# Qwiic_Shield_for_Metro_M0.net
KiCad netlist of a schematic drawn in EAGLE
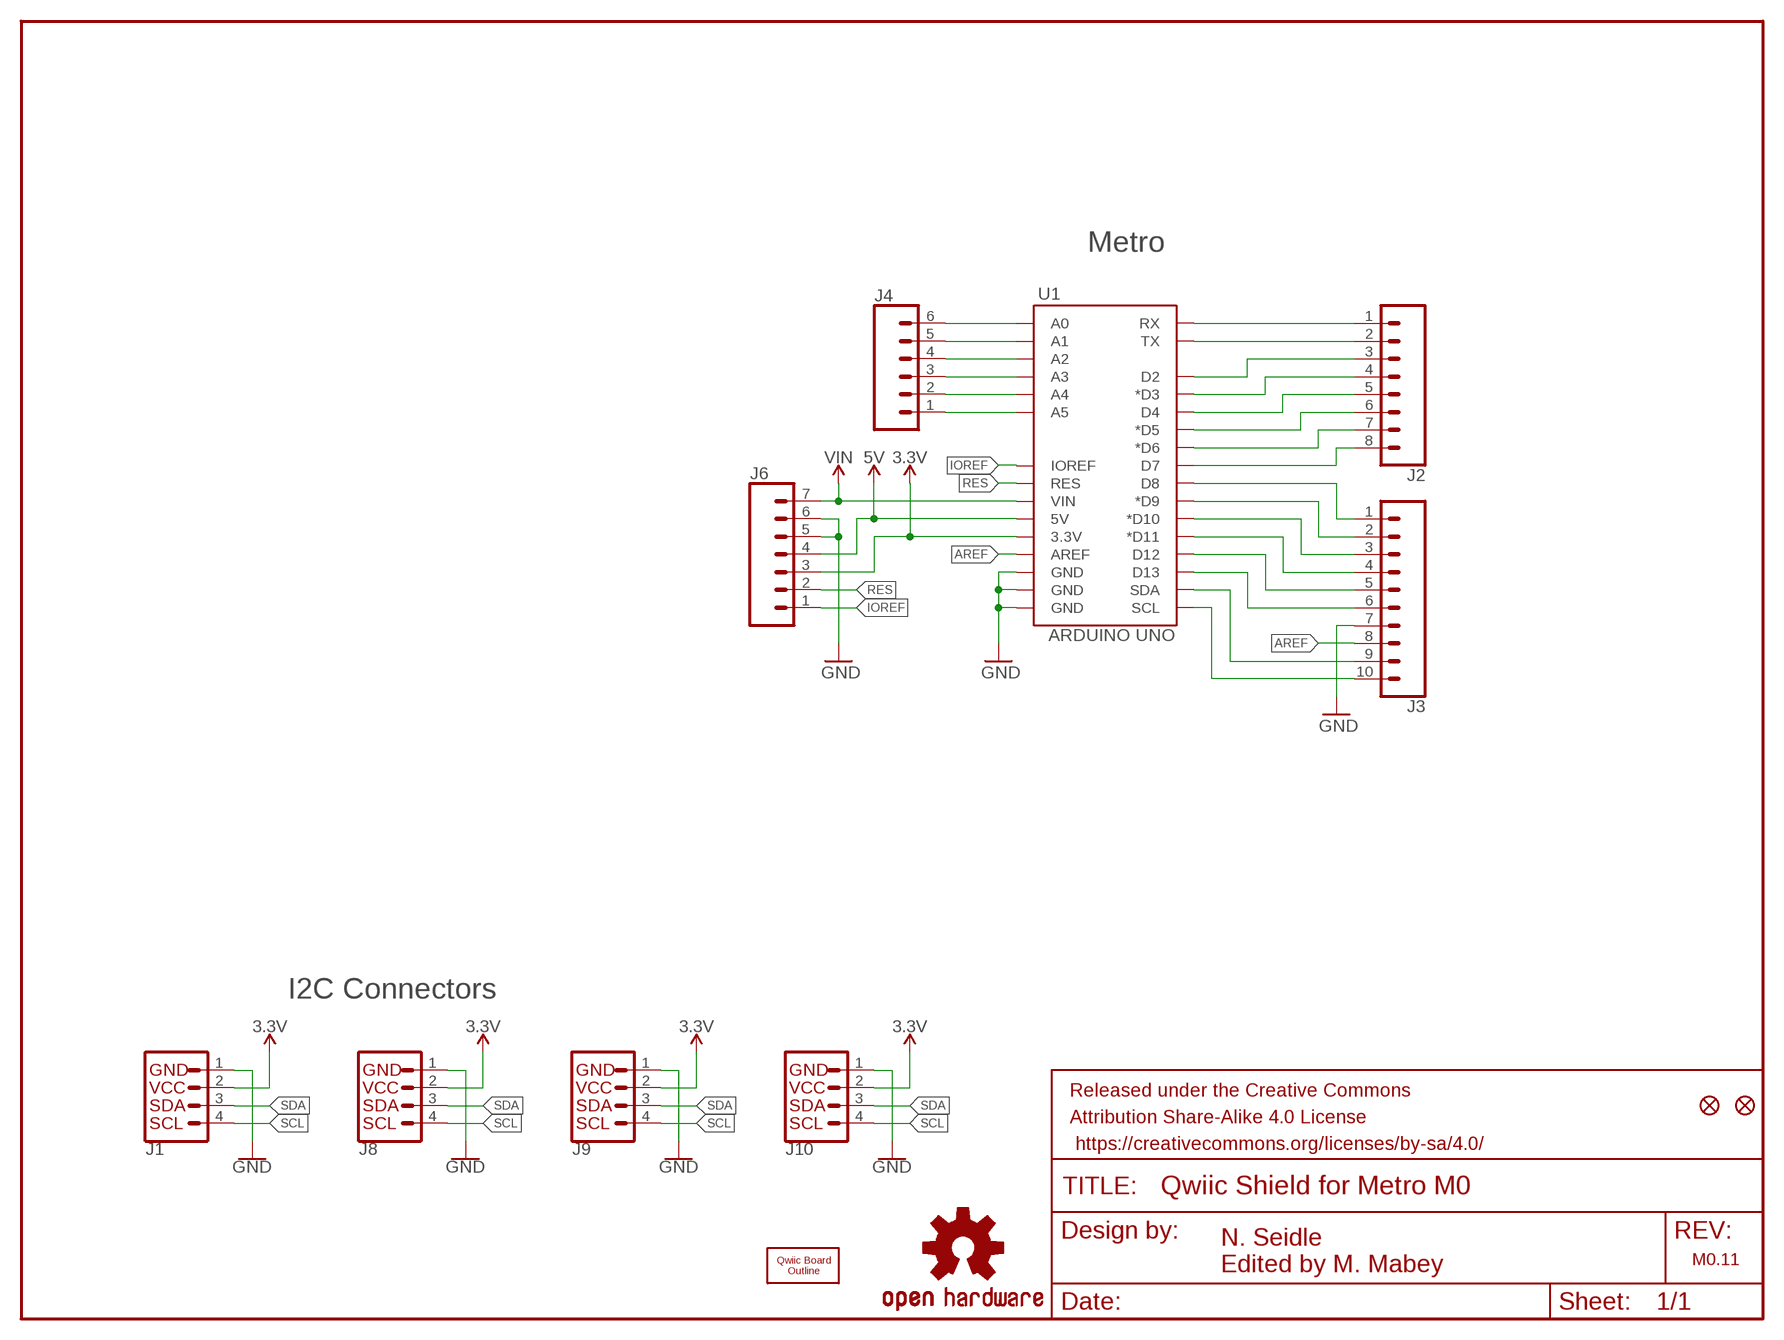
[diagram p0: schematic, sheet 1]

(export (version "E")
  (design (tool "Eeschema 10.0.6"))
  (components
    (comp (ref "FD1")
      (value "FIDUCIAL1X2")
      (footprint "eagle-import:FIDUCIAL-1X2")
      (libsource (lib "eagle-import") (part "FIDUCIAL1X2"))
    )
    (comp (ref "FD2")
      (value "FIDUCIAL1X2")
      (footprint "eagle-import:FIDUCIAL-1X2")
      (libsource (lib "eagle-import") (part "FIDUCIAL1X2"))
    )
    (comp (ref "FRAME1")
      (value "FRAME-LETTER")
      (footprint "eagle-import:CREATIVE_COMMONS")
      (libsource (lib "eagle-import") (part "FRAME-LETTER"))
    )
    (comp (ref "J1")
      (value "I2C_STANDARDJS-1MM")
      (footprint "eagle-import:1X04_1MM_RA")
      (libsource (lib "eagle-import") (part "I2C_STANDARDJS-1MM"))
    )
    (comp (ref "J2")
      (value "CONN_08NO_SILK_FEMALE_PTH")
      (footprint "eagle-import:1X08_NO_SILK")
      (libsource (lib "eagle-import") (part "CONN_08NO_SILK_FEMALE_PTH"))
    )
    (comp (ref "J3")
      (value "CONN_10NO_SILK_PTH_FEMALE")
      (footprint "eagle-import:1X10_NO_SILK")
      (libsource (lib "eagle-import") (part "CONN_10NO_SILK_PTH_FEMALE"))
    )
    (comp (ref "J4")
      (value "CONN_06NO_SILK_FEMALE_PTH")
      (footprint "eagle-import:1X06_NO_SILK")
      (libsource (lib "eagle-import") (part "CONN_06NO_SILK_FEMALE_PTH"))
    )
    (comp (ref "J6")
      (value "CONN_07NO_SILK")
      (footprint "eagle-import:1X07_NO_SILK")
      (libsource (lib "eagle-import") (part "CONN_07NO_SILK"))
    )
    (comp (ref "J8")
      (value "I2C_STANDARDJS-1MM")
      (footprint "eagle-import:1X04_1MM_RA")
      (libsource (lib "eagle-import") (part "I2C_STANDARDJS-1MM"))
    )
    (comp (ref "J9")
      (value "I2C_STANDARDJS-1MM")
      (footprint "eagle-import:1X04_1MM_RA")
      (libsource (lib "eagle-import") (part "I2C_STANDARDJS-1MM"))
    )
    (comp (ref "J10")
      (value "I2C_STANDARDJS-1MM")
      (footprint "eagle-import:1X04_1MM_RA")
      (libsource (lib "eagle-import") (part "I2C_STANDARDJS-1MM"))
    )
    (comp (ref "LOGO1")
      (value "OSHW-LOGOMINI")
      (footprint "eagle-import:OSHW-LOGO-MINI")
      (libsource (lib "eagle-import") (part "OSHW-LOGOMINI"))
    )
    (comp (ref "U$3")
      (value "QWIIC_BOARD_OUTLINEH")
      (footprint "eagle-import:QWIIC_BOARD_MOUNT_HOLES")
      (libsource (lib "eagle-import") (part "QWIIC_BOARD_OUTLINEH"))
    )
    (comp (ref "U1")
      (value "ARDUINO UNO")
      (footprint "eagle-import:UNO_R3_SHIELD_NOLABELS")
      (libsource (lib "eagle-import") (part "ARDUINO_R3_SHIELDNOLABELS"))
    )
  )
  (nets
    (net (code "1") (name "3.3V") (class "Default")
      (node (ref "J1") (pin "2") (pinfunction "VCC_2") (pintype "power_in"))
      (node (ref "J10") (pin "2") (pinfunction "VCC_2") (pintype "power_in"))
      (node (ref "J6") (pin "3") (pinfunction "3_3") (pintype "passive"))
      (node (ref "J8") (pin "2") (pinfunction "VCC_2") (pintype "power_in"))
      (node (ref "J9") (pin "2") (pinfunction "VCC_2") (pintype "power_in"))
      (node (ref "U1") (pin "3.3V") (pinfunction "3.3V_3.3V") (pintype "bidirectional"))
    )
    (net (code "2") (name "5V") (class "Default")
      (node (ref "J6") (pin "4") (pinfunction "4_4") (pintype "passive"))
      (node (ref "U1") (pin "5V") (pinfunction "5V_5V") (pintype "bidirectional"))
    )
    (net (code "3") (name "AREF") (class "Default")
      (node (ref "J3") (pin "8") (pinfunction "8_8") (pintype "passive"))
      (node (ref "U1") (pin "AREF") (pinfunction "AREF_AREF") (pintype "bidirectional"))
    )
    (net (code "4") (name "GND") (class "Default")
      (node (ref "J1") (pin "1") (pinfunction "GND_1") (pintype "power_in"))
      (node (ref "J10") (pin "1") (pinfunction "GND_1") (pintype "power_in"))
      (node (ref "J3") (pin "7") (pinfunction "7_7") (pintype "passive"))
      (node (ref "J6") (pin "5") (pinfunction "5_5") (pintype "passive"))
      (node (ref "J6") (pin "6") (pinfunction "6_6") (pintype "passive"))
      (node (ref "J8") (pin "1") (pinfunction "GND_1") (pintype "power_in"))
      (node (ref "J9") (pin "1") (pinfunction "GND_1") (pintype "power_in"))
      (node (ref "U1") (pin "GND@0") (pinfunction "GND_GND@0") (pintype "bidirectional"))
      (node (ref "U1") (pin "GND@1") (pinfunction "GND_GND@1") (pintype "bidirectional"))
      (node (ref "U1") (pin "GND@2") (pinfunction "GND_GND@2") (pintype "bidirectional"))
    )
    (net (code "5") (name "IOREF") (class "Default")
      (node (ref "J6") (pin "1") (pinfunction "1_1") (pintype "passive"))
      (node (ref "U1") (pin "IOREF") (pinfunction "IOREF_IOREF") (pintype "bidirectional"))
    )
    (net (code "6") (name "Net-(J2-Pad1)") (class "Default")
      (node (ref "J2") (pin "1") (pinfunction "1_1") (pintype "passive"))
      (node (ref "U1") (pin "RX") (pinfunction "RX_RX") (pintype "bidirectional"))
    )
    (net (code "7") (name "Net-(J2-Pad2)") (class "Default")
      (node (ref "J2") (pin "2") (pinfunction "2_2") (pintype "passive"))
      (node (ref "U1") (pin "TX") (pinfunction "TX_TX") (pintype "bidirectional"))
    )
    (net (code "8") (name "Net-(J2-Pad3)") (class "Default")
      (node (ref "J2") (pin "3") (pinfunction "3_3") (pintype "passive"))
      (node (ref "U1") (pin "D2") (pinfunction "D2_D2") (pintype "bidirectional"))
    )
    (net (code "9") (name "Net-(J2-Pad5)") (class "Default")
      (node (ref "J2") (pin "5") (pinfunction "5_5") (pintype "passive"))
      (node (ref "U1") (pin "D4") (pinfunction "D4_D4") (pintype "bidirectional"))
    )
    (net (code "10") (name "Net-(J2-Pad8)") (class "Default")
      (node (ref "J2") (pin "8") (pinfunction "8_8") (pintype "passive"))
      (node (ref "U1") (pin "D7") (pinfunction "D7_D7") (pintype "bidirectional"))
    )
    (net (code "11") (name "Net-(J3-Pad1)") (class "Default")
      (node (ref "J3") (pin "1") (pinfunction "1_1") (pintype "passive"))
      (node (ref "U1") (pin "D8") (pinfunction "D8_D8") (pintype "bidirectional"))
    )
    (net (code "12") (name "Net-(J3-Pad5)") (class "Default")
      (node (ref "J3") (pin "5") (pinfunction "5_5") (pintype "passive"))
      (node (ref "U1") (pin "D12") (pinfunction "D12_D12") (pintype "bidirectional"))
    )
    (net (code "13") (name "Net-(J3-Pad6)") (class "Default")
      (node (ref "J3") (pin "6") (pinfunction "6_6") (pintype "passive"))
      (node (ref "U1") (pin "D13") (pinfunction "D13_D13") (pintype "bidirectional"))
    )
    (net (code "14") (name "Net-(J4-Pad1)") (class "Default")
      (node (ref "J4") (pin "1") (pinfunction "1_1") (pintype "passive"))
      (node (ref "U1") (pin "A5") (pinfunction "A5_A5") (pintype "bidirectional"))
    )
    (net (code "15") (name "Net-(J4-Pad2)") (class "Default")
      (node (ref "J4") (pin "2") (pinfunction "2_2") (pintype "passive"))
      (node (ref "U1") (pin "A4") (pinfunction "A4_A4") (pintype "bidirectional"))
    )
    (net (code "16") (name "Net-(J4-Pad3)") (class "Default")
      (node (ref "J4") (pin "3") (pinfunction "3_3") (pintype "passive"))
      (node (ref "U1") (pin "A3") (pinfunction "A3_A3") (pintype "bidirectional"))
    )
    (net (code "17") (name "Net-(J4-Pad4)") (class "Default")
      (node (ref "J4") (pin "4") (pinfunction "4_4") (pintype "passive"))
      (node (ref "U1") (pin "A2") (pinfunction "A2_A2") (pintype "bidirectional"))
    )
    (net (code "18") (name "Net-(J4-Pad5)") (class "Default")
      (node (ref "J4") (pin "5") (pinfunction "5_5") (pintype "passive"))
      (node (ref "U1") (pin "A1") (pinfunction "A1_A1") (pintype "bidirectional"))
    )
    (net (code "19") (name "Net-(J4-Pad6)") (class "Default")
      (node (ref "J4") (pin "6") (pinfunction "6_6") (pintype "passive"))
      (node (ref "U1") (pin "A0") (pinfunction "A0_A0") (pintype "bidirectional"))
    )
    (net (code "20") (name "Net-(U1-*D3)") (class "Default")
      (node (ref "J2") (pin "4") (pinfunction "4_4") (pintype "passive"))
      (node (ref "U1") (pin "D3") (pinfunction "*D3_D3") (pintype "bidirectional"))
    )
    (net (code "21") (name "Net-(U1-*D5)") (class "Default")
      (node (ref "J2") (pin "6") (pinfunction "6_6") (pintype "passive"))
      (node (ref "U1") (pin "D5") (pinfunction "*D5_D5") (pintype "bidirectional"))
    )
    (net (code "22") (name "Net-(U1-*D6)") (class "Default")
      (node (ref "J2") (pin "7") (pinfunction "7_7") (pintype "passive"))
      (node (ref "U1") (pin "D6") (pinfunction "*D6_D6") (pintype "bidirectional"))
    )
    (net (code "23") (name "Net-(U1-*D9)") (class "Default")
      (node (ref "J3") (pin "2") (pinfunction "2_2") (pintype "passive"))
      (node (ref "U1") (pin "D9") (pinfunction "*D9_D9") (pintype "bidirectional"))
    )
    (net (code "24") (name "Net-(U1-*D10)") (class "Default")
      (node (ref "J3") (pin "3") (pinfunction "3_3") (pintype "passive"))
      (node (ref "U1") (pin "D10") (pinfunction "*D10_D10") (pintype "bidirectional"))
    )
    (net (code "25") (name "Net-(U1-*D11)") (class "Default")
      (node (ref "J3") (pin "4") (pinfunction "4_4") (pintype "passive"))
      (node (ref "U1") (pin "D11") (pinfunction "*D11_D11") (pintype "bidirectional"))
    )
    (net (code "26") (name "RES") (class "Default")
      (node (ref "J6") (pin "2") (pinfunction "2_2") (pintype "passive"))
      (node (ref "U1") (pin "RES") (pinfunction "RES_RES") (pintype "bidirectional"))
    )
    (net (code "27") (name "SCL") (class "Default")
      (node (ref "J1") (pin "4") (pinfunction "SCL_4") (pintype "passive"))
      (node (ref "J10") (pin "4") (pinfunction "SCL_4") (pintype "passive"))
      (node (ref "J3") (pin "10") (pinfunction "10_10") (pintype "passive"))
      (node (ref "J8") (pin "4") (pinfunction "SCL_4") (pintype "passive"))
      (node (ref "J9") (pin "4") (pinfunction "SCL_4") (pintype "passive"))
      (node (ref "U1") (pin "SCL") (pinfunction "SCL_SCL") (pintype "bidirectional"))
    )
    (net (code "28") (name "SDA") (class "Default")
      (node (ref "J1") (pin "3") (pinfunction "SDA_3") (pintype "passive"))
      (node (ref "J10") (pin "3") (pinfunction "SDA_3") (pintype "passive"))
      (node (ref "J3") (pin "9") (pinfunction "9_9") (pintype "passive"))
      (node (ref "J8") (pin "3") (pinfunction "SDA_3") (pintype "passive"))
      (node (ref "J9") (pin "3") (pinfunction "SDA_3") (pintype "passive"))
      (node (ref "U1") (pin "SDA") (pinfunction "SDA_SDA") (pintype "bidirectional"))
    )
    (net (code "29") (name "VIN") (class "Default")
      (node (ref "J6") (pin "7") (pinfunction "7_7") (pintype "passive"))
      (node (ref "U1") (pin "VIN") (pinfunction "VIN_VIN") (pintype "bidirectional"))
    )
  )
)
